# PhoneGimbal_v3.net
KiCad netlist of a schematic drawn in EAGLE
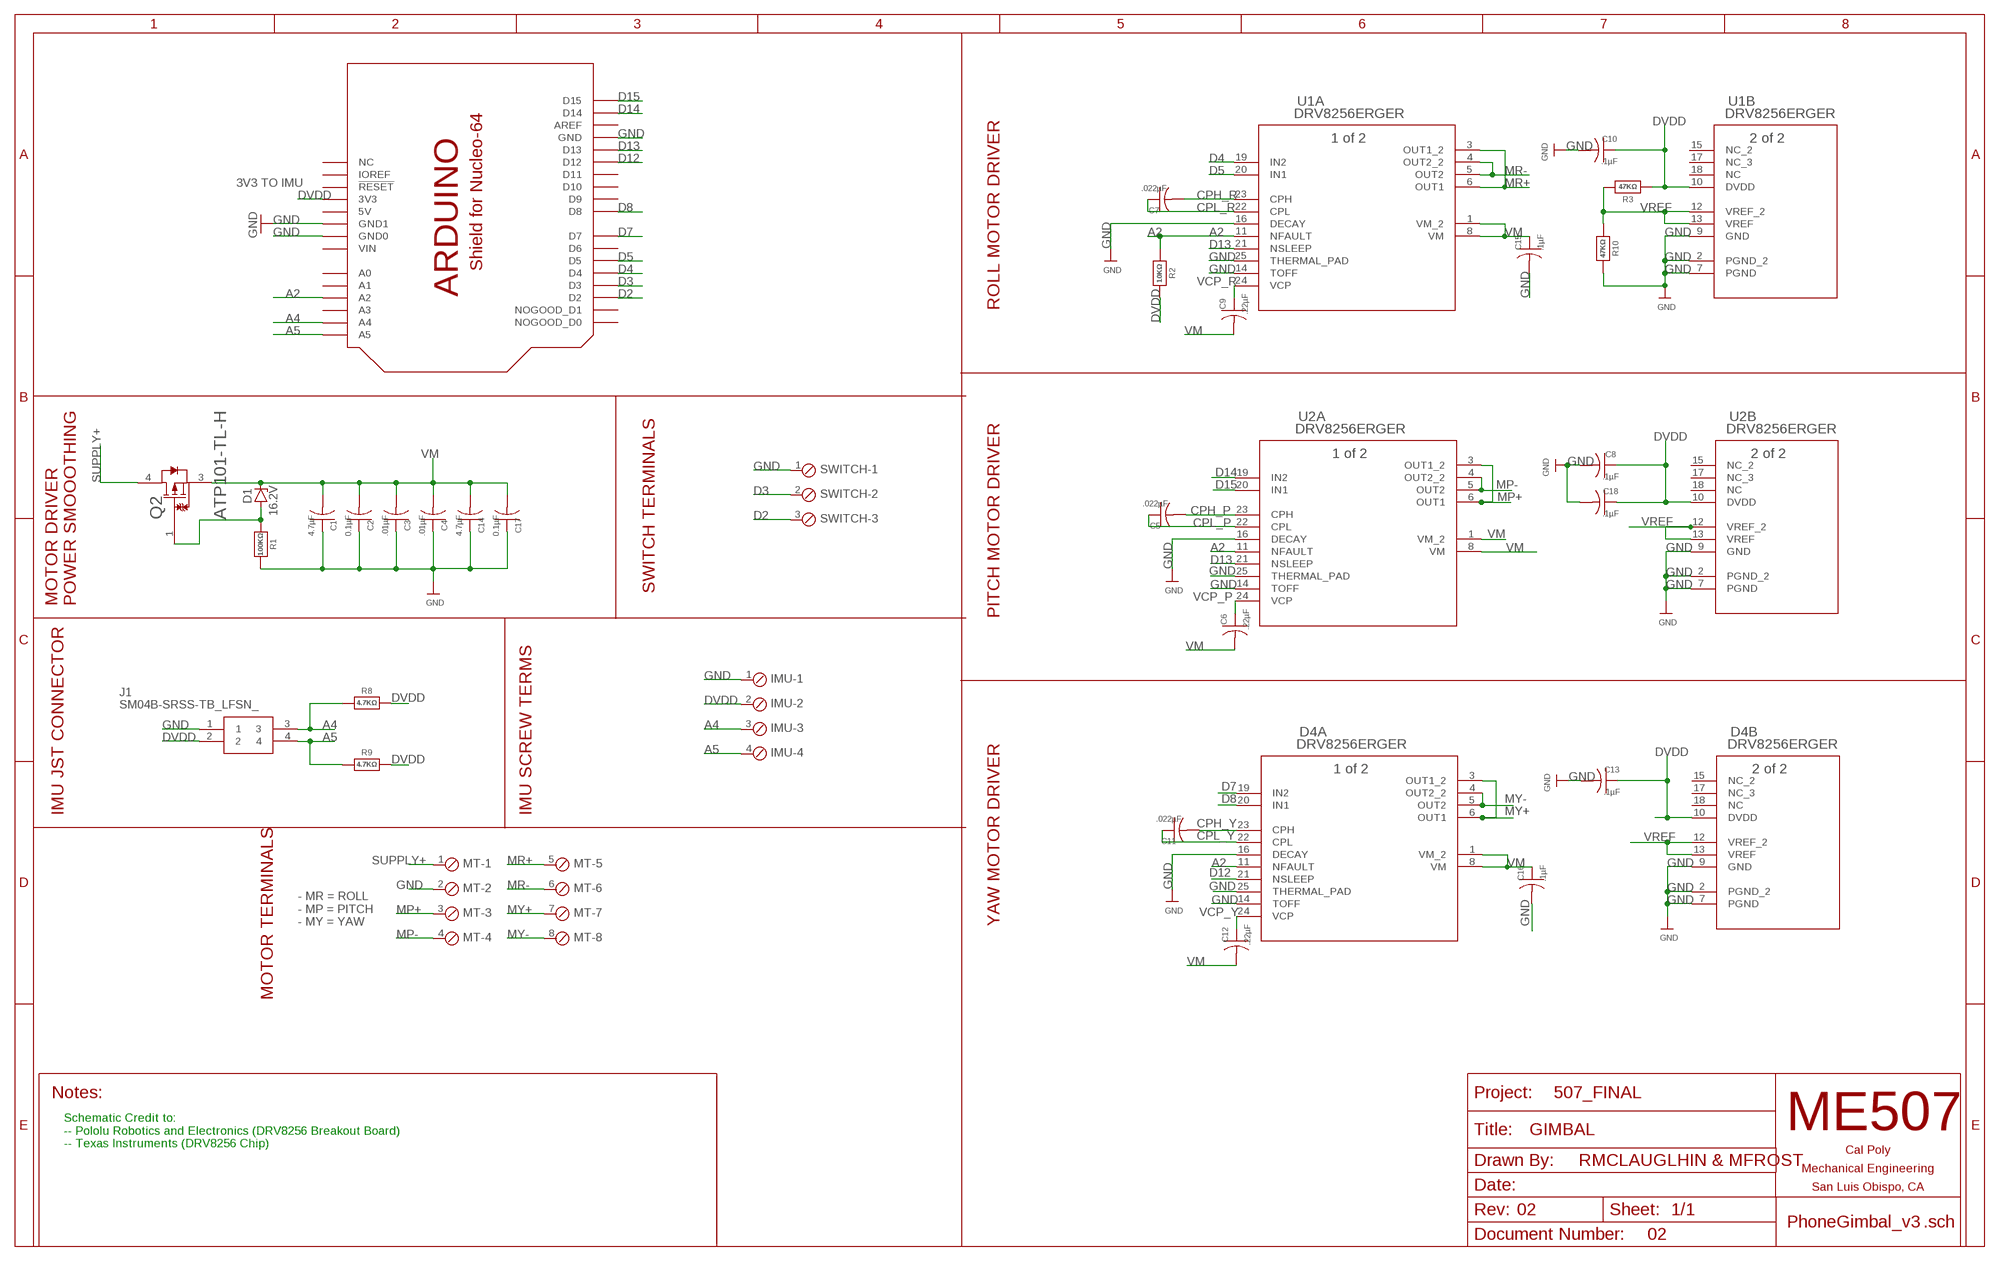
[diagram p0: schematic, sheet 1]

(export (version "E")
  (design (tool "Eeschema 10.0.6"))
  (components
    (comp (ref "C1")
      (value "4.7µF")
      (footprint "eagle-import:C0805")
      (libsource (lib "eagle-import") (part "C-USC0805"))
    )
    (comp (ref "C2")
      (value "0.1µF")
      (footprint "eagle-import:C0805")
      (libsource (lib "eagle-import") (part "C-USC0805"))
    )
    (comp (ref "C3")
      (value ".01µF")
      (footprint "eagle-import:C0805")
      (libsource (lib "eagle-import") (part "C-USC0805"))
    )
    (comp (ref "C4")
      (value ".01µF")
      (footprint "eagle-import:C0805")
      (libsource (lib "eagle-import") (part "C-USC0805"))
    )
    (comp (ref "C5")
      (value ".022µF")
      (footprint "eagle-import:C0805")
      (libsource (lib "eagle-import") (part "C-USC0805"))
    )
    (comp (ref "C6")
      (value ".22µF")
      (footprint "eagle-import:C0805")
      (libsource (lib "eagle-import") (part "C-USC0805"))
    )
    (comp (ref "C7")
      (value ".022µF")
      (footprint "eagle-import:C0805")
      (libsource (lib "eagle-import") (part "C-USC0805"))
    )
    (comp (ref "C8")
      (value ".1µF")
      (footprint "eagle-import:C0805")
      (libsource (lib "eagle-import") (part "C-USC0805"))
    )
    (comp (ref "C9")
      (value ".22µF")
      (footprint "eagle-import:C0805")
      (libsource (lib "eagle-import") (part "C-USC0805"))
    )
    (comp (ref "C10")
      (value ".1µF")
      (footprint "eagle-import:C0805")
      (libsource (lib "eagle-import") (part "C-USC0805"))
    )
    (comp (ref "C11")
      (value ".022µF")
      (footprint "eagle-import:C0805")
      (libsource (lib "eagle-import") (part "C-USC0805"))
    )
    (comp (ref "C12")
      (value ".22µF")
      (footprint "eagle-import:C0805")
      (libsource (lib "eagle-import") (part "C-USC0805"))
    )
    (comp (ref "C13")
      (value ".1µF")
      (footprint "eagle-import:C0805")
      (libsource (lib "eagle-import") (part "C-USC0805"))
    )
    (comp (ref "C14")
      (value "4.7µF")
      (footprint "eagle-import:C0805")
      (libsource (lib "eagle-import") (part "C-USC0805"))
    )
    (comp (ref "C15")
      (value ".1µF")
      (footprint "eagle-import:C0805")
      (libsource (lib "eagle-import") (part "C-USC0805"))
    )
    (comp (ref "C16")
      (value ".1µF")
      (footprint "eagle-import:C0805")
      (libsource (lib "eagle-import") (part "C-USC0805"))
    )
    (comp (ref "C17")
      (value "0.1µF")
      (footprint "eagle-import:C0805")
      (libsource (lib "eagle-import") (part "C-USC0805"))
    )
    (comp (ref "C18")
      (value ".1µF")
      (footprint "eagle-import:C0805")
      (libsource (lib "eagle-import") (part "C-USC0805"))
    )
    (comp (ref "D1")
      (value "16.2V")
      (footprint "eagle-import:DO34Z7")
      (libsource (lib "eagle-import") (part "ZENER-DIODEDO34-7"))
    )
    (comp (ref "D4")
      (value "DRV8256ERGER")
      (footprint "eagle-import:VQFN_6PRGER_TEX")
      (fields (field (name "COPYRIGHT") "Copyright (C) 2018 Accelerated Designs. All rights reserved"))
      (libsource (lib "eagle-import") (part "DRV8256ERGER"))
    )
    (comp (ref "IMU")
      (value "SCREWTERM_4P_254")
      (footprint "eagle-import:4POL254")
      (libsource (lib "eagle-import") (part "SCREWTERM_4P_254"))
    )
    (comp (ref "J1")
      (value "SM04B-SRSS-TB_LFSN_")
      (footprint "eagle-import:SM04B-SRSS-TB(LFSN)")
      (fields (field (name "MANUFACTURER_PART_NUMBER") "SM04B-SRSS-TB(LFSN)"))
      (libsource (lib "eagle-import") (part "SM04B-SRSS-TB_LFSN_"))
    )
    (comp (ref "MT")
      (value "SCREWTERM_8P_381")
      (footprint "eagle-import:8POL381")
      (libsource (lib "eagle-import") (part "SCREWTERM_8P_381"))
    )
    (comp (ref "Q2")
      (value "ON_SEMICONDUCTOR_ATP101-TL-HON_SEMICONDUCTOR_ATP101-TL-H_0_0")
      (footprint "eagle-import:ON_SEMICONDUCTOR_ATP101-TL-H_0")
      (fields (field (name "MF") "On Semiconductor") (field (name "MPN") "ATP101-TL-H"))
      (libsource (lib "eagle-import") (part "ON_SEMICONDUCTOR_ATP101-TL-HON_SEMICONDUCTOR_ATP101-TL-H_0_0"))
    )
    (comp (ref "R1")
      (value "100KΩ")
      (footprint "eagle-import:_1206")
      (libsource (lib "eagle-import") (part "RESISTOR_1206"))
    )
    (comp (ref "R2")
      (value "10KΩ")
      (footprint "eagle-import:_1206")
      (libsource (lib "eagle-import") (part "RESISTOR_1206"))
    )
    (comp (ref "R3")
      (value "47KΩ")
      (footprint "eagle-import:_1206")
      (libsource (lib "eagle-import") (part "RESISTOR_1206"))
    )
    (comp (ref "R8")
      (value "4.7KΩ")
      (footprint "eagle-import:_1206")
      (libsource (lib "eagle-import") (part "RESISTOR_1206"))
    )
    (comp (ref "R9")
      (value "4.7KΩ")
      (footprint "eagle-import:_1206")
      (libsource (lib "eagle-import") (part "RESISTOR_1206"))
    )
    (comp (ref "R10")
      (value "47KΩ")
      (footprint "eagle-import:_1206")
      (libsource (lib "eagle-import") (part "RESISTOR_1206"))
    )
    (comp (ref "SWITCH")
      (value "SCREWTERM_3P_254")
      (footprint "eagle-import:3POL254")
      (libsource (lib "eagle-import") (part "SCREWTERM_3P_254"))
    )
    (comp (ref "U$1")
      (value "SHIELD_FOR_NUCLE0_64_STANDARD")
      (footprint "eagle-import:SHIELD_FOR_NUCLEO_64_STD")
      (libsource (lib "eagle-import") (part "SHIELD_FOR_NUCLE0_64_STANDARD"))
    )
    (comp (ref "U1")
      (value "DRV8256ERGER")
      (footprint "eagle-import:VQFN_6PRGER_TEX")
      (fields (field (name "COPYRIGHT") "Copyright (C) 2018 Accelerated Designs. All rights reserved"))
      (libsource (lib "eagle-import") (part "DRV8256ERGER"))
    )
    (comp (ref "U2")
      (value "DRV8256ERGER")
      (footprint "eagle-import:VQFN_6PRGER_TEX")
      (fields (field (name "COPYRIGHT") "Copyright (C) 2018 Accelerated Designs. All rights reserved"))
      (libsource (lib "eagle-import") (part "DRV8256ERGER"))
    )
  )
  (nets
    (net (code "1") (name "/5V") (class "Default")
      (node (ref "U$1") (pin "5V") (pinfunction "5V_5V") (pintype "power_in"))
    )
    (net (code "2") (name "/A2") (class "Default")
      (node (ref "D4") (pin "11") (pinfunction "NFAULT_11") (pintype "passive"))
      (node (ref "R2") (pin "1") (pinfunction "1_1") (pintype "passive"))
      (node (ref "U$1") (pin "A2") (pinfunction "A2_A2") (pintype "bidirectional"))
      (node (ref "U1") (pin "11") (pinfunction "NFAULT_11") (pintype "passive"))
      (node (ref "U2") (pin "11") (pinfunction "NFAULT_11") (pintype "passive"))
    )
    (net (code "3") (name "/A4") (class "Default")
      (node (ref "IMU") (pin "3") (pinfunction "1_3") (pintype "passive"))
      (node (ref "J1") (pin "3") (pinfunction "3_3") (pintype "bidirectional"))
      (node (ref "R8") (pin "1") (pinfunction "1_1") (pintype "passive"))
      (node (ref "U$1") (pin "A4") (pinfunction "A4_A4") (pintype "bidirectional"))
    )
    (net (code "4") (name "/A5") (class "Default")
      (node (ref "IMU") (pin "4") (pinfunction "1_4") (pintype "passive"))
      (node (ref "J1") (pin "4") (pinfunction "4_4") (pintype "bidirectional"))
      (node (ref "R9") (pin "1") (pinfunction "1_1") (pintype "passive"))
      (node (ref "U$1") (pin "A5") (pinfunction "A5_A5") (pintype "bidirectional"))
    )
    (net (code "5") (name "/CPH_P") (class "Default")
      (node (ref "C5") (pin "2") (pinfunction "2_2") (pintype "passive"))
      (node (ref "U2") (pin "23") (pinfunction "CPH_23") (pintype "passive"))
    )
    (net (code "6") (name "/CPH_R") (class "Default")
      (node (ref "C7") (pin "2") (pinfunction "2_2") (pintype "passive"))
      (node (ref "U1") (pin "23") (pinfunction "CPH_23") (pintype "passive"))
    )
    (net (code "7") (name "/CPH_Y") (class "Default")
      (node (ref "C11") (pin "2") (pinfunction "2_2") (pintype "passive"))
      (node (ref "D4") (pin "23") (pinfunction "CPH_23") (pintype "passive"))
    )
    (net (code "8") (name "/CPL_P") (class "Default")
      (node (ref "C5") (pin "1") (pinfunction "1_1") (pintype "passive"))
      (node (ref "U2") (pin "22") (pinfunction "CPL_22") (pintype "passive"))
    )
    (net (code "9") (name "/CPL_R") (class "Default")
      (node (ref "C7") (pin "1") (pinfunction "1_1") (pintype "passive"))
      (node (ref "U1") (pin "22") (pinfunction "CPL_22") (pintype "passive"))
    )
    (net (code "10") (name "/CPL_Y") (class "Default")
      (node (ref "C11") (pin "1") (pinfunction "1_1") (pintype "passive"))
      (node (ref "D4") (pin "22") (pinfunction "CPL_22") (pintype "passive"))
    )
    (net (code "11") (name "/D2") (class "Default")
      (node (ref "SWITCH") (pin "3") (pinfunction "1_3") (pintype "passive"))
      (node (ref "U$1") (pin "D2") (pinfunction "D2_D2") (pintype "bidirectional"))
    )
    (net (code "12") (name "/D3") (class "Default")
      (node (ref "SWITCH") (pin "2") (pinfunction "1_2") (pintype "passive"))
      (node (ref "U$1") (pin "D3") (pinfunction "D3_D3") (pintype "bidirectional"))
    )
    (net (code "13") (name "/D4") (class "Default")
      (node (ref "U$1") (pin "D4") (pinfunction "D4_D4") (pintype "bidirectional"))
      (node (ref "U1") (pin "19") (pinfunction "IN2_19") (pintype "input"))
    )
    (net (code "14") (name "/D5") (class "Default")
      (node (ref "U$1") (pin "D5") (pinfunction "D5_D5") (pintype "bidirectional"))
      (node (ref "U1") (pin "20") (pinfunction "IN1_20") (pintype "input"))
    )
    (net (code "15") (name "/D7") (class "Default")
      (node (ref "D4") (pin "19") (pinfunction "IN2_19") (pintype "input"))
      (node (ref "U$1") (pin "D7") (pinfunction "D7_D7") (pintype "bidirectional"))
    )
    (net (code "16") (name "/D8") (class "Default")
      (node (ref "D4") (pin "20") (pinfunction "IN1_20") (pintype "input"))
      (node (ref "U$1") (pin "D8") (pinfunction "D8_D8") (pintype "bidirectional"))
    )
    (net (code "17") (name "/D12") (class "Default")
      (node (ref "D4") (pin "21") (pinfunction "NSLEEP_21") (pintype "passive"))
      (node (ref "U$1") (pin "D12") (pinfunction "D12_D12") (pintype "bidirectional"))
    )
    (net (code "18") (name "/D13") (class "Default")
      (node (ref "U$1") (pin "D13") (pinfunction "D13_D13") (pintype "bidirectional"))
      (node (ref "U1") (pin "21") (pinfunction "NSLEEP_21") (pintype "passive"))
      (node (ref "U2") (pin "21") (pinfunction "NSLEEP_21") (pintype "passive"))
    )
    (net (code "19") (name "/D14") (class "Default")
      (node (ref "U$1") (pin "D14") (pinfunction "D14_D14") (pintype "bidirectional"))
      (node (ref "U2") (pin "19") (pinfunction "IN2_19") (pintype "input"))
    )
    (net (code "20") (name "/D15") (class "Default")
      (node (ref "U$1") (pin "D15") (pinfunction "D15_D15") (pintype "bidirectional"))
      (node (ref "U2") (pin "20") (pinfunction "IN1_20") (pintype "input"))
    )
    (net (code "21") (name "/DVDD") (class "Default")
      (node (ref "C10") (pin "1") (pinfunction "1_1") (pintype "passive"))
      (node (ref "C13") (pin "1") (pinfunction "1_1") (pintype "passive"))
      (node (ref "C18") (pin "1") (pinfunction "1_1") (pintype "passive"))
      (node (ref "C8") (pin "1") (pinfunction "1_1") (pintype "passive"))
      (node (ref "D4") (pin "10") (pinfunction "DVDD_10") (pintype "power_in"))
      (node (ref "IMU") (pin "2") (pinfunction "1_2") (pintype "passive"))
      (node (ref "J1") (pin "2") (pinfunction "2_2") (pintype "bidirectional"))
      (node (ref "R2") (pin "2") (pinfunction "2_2") (pintype "passive"))
      (node (ref "R3") (pin "1") (pinfunction "1_1") (pintype "passive"))
      (node (ref "R8") (pin "2") (pinfunction "2_2") (pintype "passive"))
      (node (ref "R9") (pin "2") (pinfunction "2_2") (pintype "passive"))
      (node (ref "U$1") (pin "3V") (pinfunction "3V3_3V") (pintype "power_in"))
      (node (ref "U1") (pin "10") (pinfunction "DVDD_10") (pintype "power_in"))
      (node (ref "U2") (pin "10") (pinfunction "DVDD_10") (pintype "power_in"))
    )
    (net (code "22") (name "/MP+") (class "Default")
      (node (ref "MT") (pin "3") (pinfunction "1_3") (pintype "passive"))
      (node (ref "U2") (pin "3") (pinfunction "OUT1_2_3") (pintype "output"))
      (node (ref "U2") (pin "6") (pinfunction "OUT1_6") (pintype "output"))
    )
    (net (code "23") (name "/MP-") (class "Default")
      (node (ref "MT") (pin "4") (pinfunction "1_4") (pintype "passive"))
      (node (ref "U2") (pin "4") (pinfunction "OUT2_2_4") (pintype "output"))
      (node (ref "U2") (pin "5") (pinfunction "OUT2_5") (pintype "output"))
    )
    (net (code "24") (name "/MR+") (class "Default")
      (node (ref "MT") (pin "5") (pinfunction "1_5") (pintype "passive"))
      (node (ref "U1") (pin "3") (pinfunction "OUT1_2_3") (pintype "output"))
      (node (ref "U1") (pin "6") (pinfunction "OUT1_6") (pintype "output"))
    )
    (net (code "25") (name "/MR-") (class "Default")
      (node (ref "MT") (pin "6") (pinfunction "1_6") (pintype "passive"))
      (node (ref "U1") (pin "4") (pinfunction "OUT2_2_4") (pintype "output"))
      (node (ref "U1") (pin "5") (pinfunction "OUT2_5") (pintype "output"))
    )
    (net (code "26") (name "/MY+") (class "Default")
      (node (ref "D4") (pin "3") (pinfunction "OUT1_2_3") (pintype "output"))
      (node (ref "D4") (pin "6") (pinfunction "OUT1_6") (pintype "output"))
      (node (ref "MT") (pin "7") (pinfunction "1_7") (pintype "passive"))
    )
    (net (code "27") (name "/MY-") (class "Default")
      (node (ref "D4") (pin "4") (pinfunction "OUT2_2_4") (pintype "output"))
      (node (ref "D4") (pin "5") (pinfunction "OUT2_5") (pintype "output"))
      (node (ref "MT") (pin "8") (pinfunction "1_8") (pintype "passive"))
    )
    (net (code "28") (name "/SUPPLY+") (class "Default")
      (node (ref "MT") (pin "1") (pinfunction "1_1") (pintype "passive"))
      (node (ref "Q2") (pin "4") (pinfunction "D_4") (pintype "passive"))
    )
    (net (code "29") (name "/VCP_P") (class "Default")
      (node (ref "C6") (pin "1") (pinfunction "1_1") (pintype "passive"))
      (node (ref "U2") (pin "24") (pinfunction "VCP_24") (pintype "passive"))
    )
    (net (code "30") (name "/VCP_R") (class "Default")
      (node (ref "C9") (pin "1") (pinfunction "1_1") (pintype "passive"))
      (node (ref "U1") (pin "24") (pinfunction "VCP_24") (pintype "passive"))
    )
    (net (code "31") (name "/VCP_Y") (class "Default")
      (node (ref "C12") (pin "1") (pinfunction "1_1") (pintype "passive"))
      (node (ref "D4") (pin "24") (pinfunction "VCP_24") (pintype "passive"))
    )
    (net (code "32") (name "/VIN") (class "Default")
      (node (ref "U$1") (pin "VIN") (pinfunction "VIN_VIN") (pintype "power_in"))
    )
    (net (code "33") (name "/VM") (class "Default")
      (node (ref "C1") (pin "2") (pinfunction "2_2") (pintype "passive"))
      (node (ref "C12") (pin "2") (pinfunction "2_2") (pintype "passive"))
      (node (ref "C14") (pin "2") (pinfunction "2_2") (pintype "passive"))
      (node (ref "C15") (pin "1") (pinfunction "1_1") (pintype "passive"))
      (node (ref "C16") (pin "1") (pinfunction "1_1") (pintype "passive"))
      (node (ref "C17") (pin "2") (pinfunction "2_2") (pintype "passive"))
      (node (ref "C2") (pin "2") (pinfunction "2_2") (pintype "passive"))
      (node (ref "C3") (pin "2") (pinfunction "2_2") (pintype "passive"))
      (node (ref "C4") (pin "2") (pinfunction "2_2") (pintype "passive"))
      (node (ref "C6") (pin "2") (pinfunction "2_2") (pintype "passive"))
      (node (ref "C9") (pin "2") (pinfunction "2_2") (pintype "passive"))
      (node (ref "D1") (pin "C") (pinfunction "C_C") (pintype "passive"))
      (node (ref "D4") (pin "1") (pinfunction "VM_2_1") (pintype "passive"))
      (node (ref "D4") (pin "8") (pinfunction "VM_8") (pintype "passive"))
      (node (ref "Q2") (pin "3") (pinfunction "S_3") (pintype "passive"))
      (node (ref "U1") (pin "1") (pinfunction "VM_2_1") (pintype "passive"))
      (node (ref "U1") (pin "8") (pinfunction "VM_8") (pintype "passive"))
      (node (ref "U2") (pin "1") (pinfunction "VM_2_1") (pintype "passive"))
      (node (ref "U2") (pin "8") (pinfunction "VM_8") (pintype "passive"))
    )
    (net (code "34") (name "/VREF") (class "Default")
      (node (ref "D4") (pin "12") (pinfunction "VREF_2_12") (pintype "power_in"))
      (node (ref "D4") (pin "13") (pinfunction "VREF_13") (pintype "power_in"))
      (node (ref "R10") (pin "1") (pinfunction "1_1") (pintype "passive"))
      (node (ref "R3") (pin "2") (pinfunction "2_2") (pintype "passive"))
      (node (ref "U1") (pin "12") (pinfunction "VREF_2_12") (pintype "power_in"))
      (node (ref "U1") (pin "13") (pinfunction "VREF_13") (pintype "power_in"))
      (node (ref "U2") (pin "12") (pinfunction "VREF_2_12") (pintype "power_in"))
      (node (ref "U2") (pin "13") (pinfunction "VREF_13") (pintype "power_in"))
    )
    (net (code "35") (name "GND") (class "Default")
      (node (ref "C1") (pin "1") (pinfunction "1_1") (pintype "passive"))
      (node (ref "C10") (pin "2") (pinfunction "2_2") (pintype "passive"))
      (node (ref "C13") (pin "2") (pinfunction "2_2") (pintype "passive"))
      (node (ref "C14") (pin "1") (pinfunction "1_1") (pintype "passive"))
      (node (ref "C15") (pin "2") (pinfunction "2_2") (pintype "passive"))
      (node (ref "C16") (pin "2") (pinfunction "2_2") (pintype "passive"))
      (node (ref "C17") (pin "1") (pinfunction "1_1") (pintype "passive"))
      (node (ref "C18") (pin "2") (pinfunction "2_2") (pintype "passive"))
      (node (ref "C2") (pin "1") (pinfunction "1_1") (pintype "passive"))
      (node (ref "C3") (pin "1") (pinfunction "1_1") (pintype "passive"))
      (node (ref "C4") (pin "1") (pinfunction "1_1") (pintype "passive"))
      (node (ref "C8") (pin "2") (pinfunction "2_2") (pintype "passive"))
      (node (ref "D4") (pin "14") (pinfunction "TOFF_14") (pintype "passive"))
      (node (ref "D4") (pin "16") (pinfunction "DECAY_16") (pintype "passive"))
      (node (ref "D4") (pin "2") (pinfunction "PGND_2_2") (pintype "passive"))
      (node (ref "D4") (pin "25") (pinfunction "THERMAL_PAD_25") (pintype "passive"))
      (node (ref "D4") (pin "7") (pinfunction "PGND_7") (pintype "passive"))
      (node (ref "D4") (pin "9") (pinfunction "GND_9") (pintype "passive"))
      (node (ref "IMU") (pin "1") (pinfunction "1_1") (pintype "passive"))
      (node (ref "J1") (pin "1") (pinfunction "1_1") (pintype "bidirectional"))
      (node (ref "MT") (pin "2") (pinfunction "1_2") (pintype "passive"))
      (node (ref "R1") (pin "2") (pinfunction "2_2") (pintype "passive"))
      (node (ref "R10") (pin "2") (pinfunction "2_2") (pintype "passive"))
      (node (ref "SWITCH") (pin "1") (pinfunction "1_1") (pintype "passive"))
      (node (ref "U$1") (pin "GND") (pinfunction "GND_GND") (pintype "power_in"))
      (node (ref "U$1") (pin "GND1") (pinfunction "GND0_GND1") (pintype "power_in"))
      (node (ref "U$1") (pin "GND2") (pinfunction "GND1_GND2") (pintype "power_in"))
      (node (ref "U1") (pin "14") (pinfunction "TOFF_14") (pintype "passive"))
      (node (ref "U1") (pin "16") (pinfunction "DECAY_16") (pintype "passive"))
      (node (ref "U1") (pin "2") (pinfunction "PGND_2_2") (pintype "passive"))
      (node (ref "U1") (pin "25") (pinfunction "THERMAL_PAD_25") (pintype "passive"))
      (node (ref "U1") (pin "7") (pinfunction "PGND_7") (pintype "passive"))
      (node (ref "U1") (pin "9") (pinfunction "GND_9") (pintype "passive"))
      (node (ref "U2") (pin "14") (pinfunction "TOFF_14") (pintype "passive"))
      (node (ref "U2") (pin "16") (pinfunction "DECAY_16") (pintype "passive"))
      (node (ref "U2") (pin "2") (pinfunction "PGND_2_2") (pintype "passive"))
      (node (ref "U2") (pin "25") (pinfunction "THERMAL_PAD_25") (pintype "passive"))
      (node (ref "U2") (pin "7") (pinfunction "PGND_7") (pintype "passive"))
      (node (ref "U2") (pin "9") (pinfunction "GND_9") (pintype "passive"))
    )
    (net (code "36") (name "Net-(Q2-G)") (class "Default")
      (node (ref "D1") (pin "A") (pinfunction "A_A") (pintype "passive"))
      (node (ref "Q2") (pin "1") (pinfunction "G_1") (pintype "passive"))
      (node (ref "R1") (pin "1") (pinfunction "1_1") (pintype "passive"))
    )
    (net (code "37") (name "unconnected-(D4B-NC-Pad18)") (class "Default")
      (node (ref "D4") (pin "18") (pinfunction "NC_18") (pintype "no_connect"))
    )
    (net (code "38") (name "unconnected-(D4B-NC_2-Pad15)") (class "Default")
      (node (ref "D4") (pin "15") (pinfunction "NC_2_15") (pintype "no_connect"))
    )
    (net (code "39") (name "unconnected-(D4B-NC_3-Pad17)") (class "Default")
      (node (ref "D4") (pin "17") (pinfunction "NC_3_17") (pintype "no_connect"))
    )
    (net (code "40") (name "unconnected-(U$1-NOGOOD_D0-PadD0)") (class "Default")
      (node (ref "U$1") (pin "D0") (pinfunction "NOGOOD_D0_D0") (pintype "no_connect"))
    )
    (net (code "41") (name "unconnected-(U$1-NOGOOD_D1-PadD1)") (class "Default")
      (node (ref "U$1") (pin "D1") (pinfunction "NOGOOD_D1_D1") (pintype "no_connect"))
    )
    (net (code "42") (name "unconnected-(U$1-PadA0)") (class "Default")
      (node (ref "U$1") (pin "A0") (pinfunction "A0_A0") (pintype "bidirectional"))
    )
    (net (code "43") (name "unconnected-(U$1-PadA1)") (class "Default")
      (node (ref "U$1") (pin "A1") (pinfunction "A1_A1") (pintype "bidirectional"))
    )
    (net (code "44") (name "unconnected-(U$1-PadA3)") (class "Default")
      (node (ref "U$1") (pin "A3") (pinfunction "A3_A3") (pintype "bidirectional"))
    )
    (net (code "45") (name "unconnected-(U$1-PadAREF)") (class "Default")
      (node (ref "U$1") (pin "AREF") (pinfunction "AREF_AREF") (pintype "bidirectional"))
    )
    (net (code "46") (name "unconnected-(U$1-PadD6)") (class "Default")
      (node (ref "U$1") (pin "D6") (pinfunction "D6_D6") (pintype "bidirectional"))
    )
    (net (code "47") (name "unconnected-(U$1-PadD9)") (class "Default")
      (node (ref "U$1") (pin "D9") (pinfunction "D9_D9") (pintype "bidirectional"))
    )
    (net (code "48") (name "unconnected-(U$1-PadD10)") (class "Default")
      (node (ref "U$1") (pin "D10") (pinfunction "D10_D10") (pintype "bidirectional"))
    )
    (net (code "49") (name "unconnected-(U$1-PadD11)") (class "Default")
      (node (ref "U$1") (pin "D11") (pinfunction "D11_D11") (pintype "bidirectional"))
    )
    (net (code "50") (name "unconnected-(U$1-PadIOREF)") (class "Default")
      (node (ref "U$1") (pin "IOREF") (pinfunction "IOREF_IOREF") (pintype "bidirectional"))
    )
    (net (code "51") (name "unconnected-(U$1-PadNC)") (class "Default")
      (node (ref "U$1") (pin "NC") (pinfunction "NC_NC") (pintype "no_connect"))
    )
    (net (code "52") (name "unconnected-(U$1-~{RESET}-PadNRST)") (class "Default")
      (node (ref "U$1") (pin "NRST") (pinfunction "~{RESET}_NRST") (pintype "input"))
    )
    (net (code "53") (name "unconnected-(U1B-NC-Pad18)") (class "Default")
      (node (ref "U1") (pin "18") (pinfunction "NC_18") (pintype "no_connect"))
    )
    (net (code "54") (name "unconnected-(U1B-NC_2-Pad15)") (class "Default")
      (node (ref "U1") (pin "15") (pinfunction "NC_2_15") (pintype "no_connect"))
    )
    (net (code "55") (name "unconnected-(U1B-NC_3-Pad17)") (class "Default")
      (node (ref "U1") (pin "17") (pinfunction "NC_3_17") (pintype "no_connect"))
    )
    (net (code "56") (name "unconnected-(U2B-NC-Pad18)") (class "Default")
      (node (ref "U2") (pin "18") (pinfunction "NC_18") (pintype "no_connect"))
    )
    (net (code "57") (name "unconnected-(U2B-NC_2-Pad15)") (class "Default")
      (node (ref "U2") (pin "15") (pinfunction "NC_2_15") (pintype "no_connect"))
    )
    (net (code "58") (name "unconnected-(U2B-NC_3-Pad17)") (class "Default")
      (node (ref "U2") (pin "17") (pinfunction "NC_3_17") (pintype "no_connect"))
    )
  )
)
